# Sheet1.net
KiCad netlist of a schematic drawn in Altium Designer
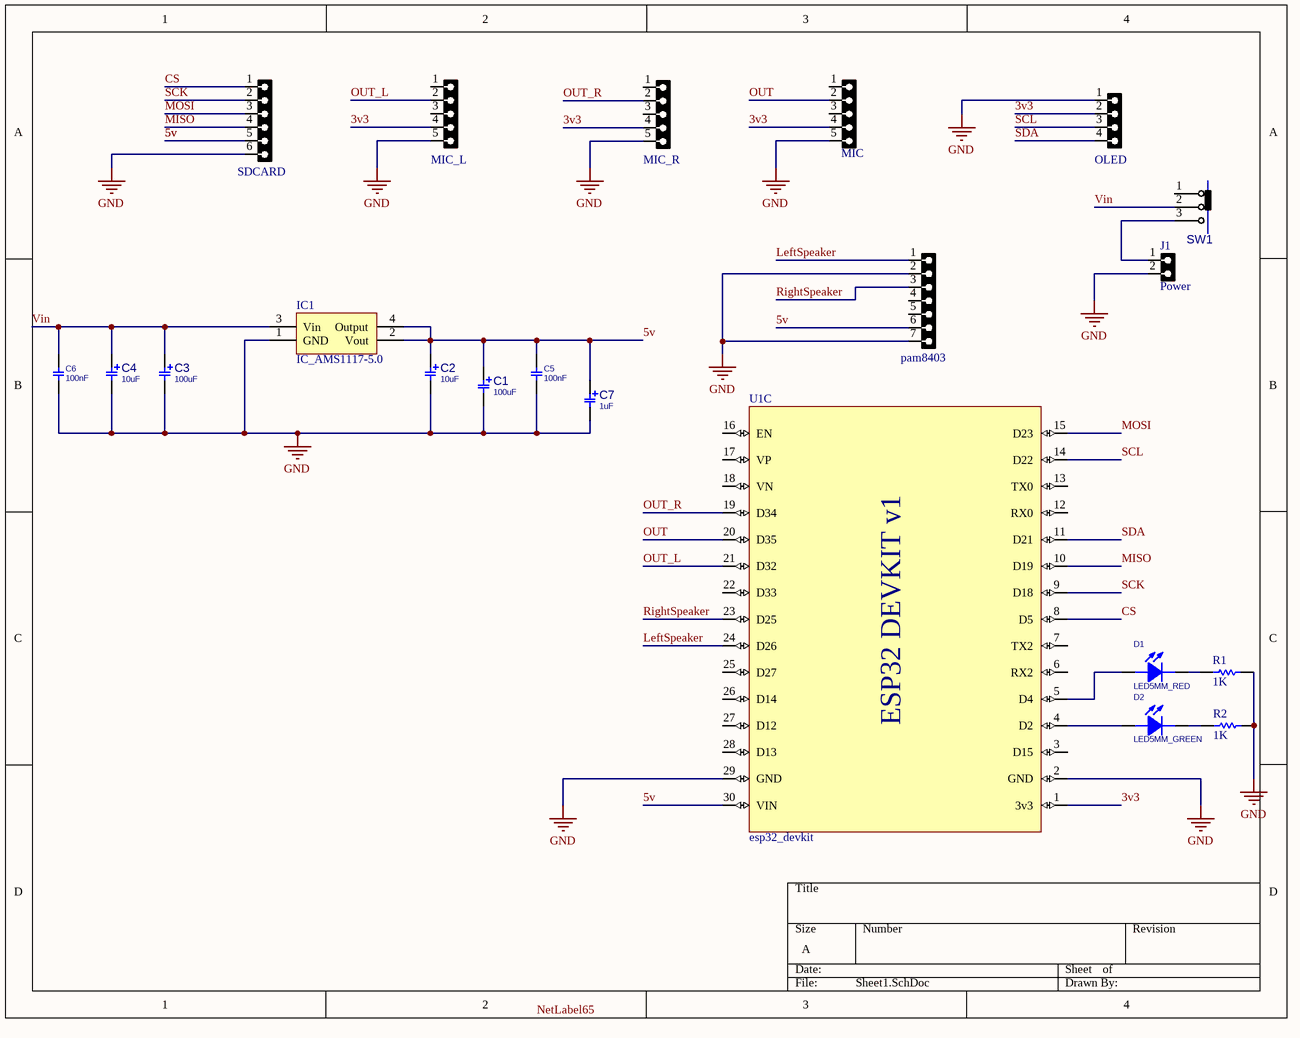
[diagram p0: Sheet1.SchDoc]

(export (version "E")
  (design (tool "Eeschema 10.0.6"))
  (components
    (comp (ref "C1")
      (value "100uF")
      (footprint "C_EL_4X7")
      (description "CAP, THD, ELEC,")
      (fields (field (name "MANF_P#") "MANF_PART#") (field (name "MANF") "MANF"))
      (libsource (lib "passive_thd") (part "CAP_THD_EL_4X7"))
    )
    (comp (ref "C2")
      (value "10uF")
      (footprint "C_EL_4X7")
      (description "CAP, THD, ELEC,")
      (fields (field (name "MANF_P#") "MANF_PART#") (field (name "MANF") "MANF"))
      (libsource (lib "passive_thd") (part "CAP_THD_EL_4X7"))
    )
    (comp (ref "C3")
      (value "100uF")
      (footprint "C_EL_4X7")
      (description "CAP, THD, ELEC,")
      (fields (field (name "MANF_P#") "MANF_PART#") (field (name "MANF") "MANF"))
      (libsource (lib "passive_thd") (part "CAP_THD_EL_4X7"))
    )
    (comp (ref "C4")
      (value "10uF")
      (footprint "C_EL_4X7")
      (description "CAP, THD, ELEC,")
      (fields (field (name "MANF_P#") "MANF_PART#") (field (name "MANF") "MANF"))
      (libsource (lib "passive_thd") (part "CAP_THD_EL_4X7"))
    )
    (comp (ref "C5")
      (value "100nF")
      (footprint "C_CER_D3")
      (description "CAP, THD, CER MULTI LAYER,")
      (fields (field (name "MANF_P#") "MANF_PART#") (field (name "MANF") "MANF"))
      (libsource (lib "passive_thd") (part "CAP_THD_CERML"))
    )
    (comp (ref "C6")
      (value "100nF")
      (footprint "C_CER_D3")
      (description "CAP, THD, CER MULTI LAYER,")
      (fields (field (name "MANF_P#") "MANF_PART#") (field (name "MANF") "MANF"))
      (libsource (lib "passive_thd") (part "CAP_THD_CERML"))
    )
    (comp (ref "C7")
      (value "1uF")
      (footprint "C_EL_4X7")
      (description "CAP, THD, ELEC,")
      (fields (field (name "MANF_P#") "MANF_PART#") (field (name "MANF") "MANF"))
      (libsource (lib "passive_thd") (part "CAP_THD_EL_4X7"))
    )
    (comp (ref "D1")
      (value "LED5MM_RED")
      (footprint "LED5MM_RED")
      (description "LED LIGHTING")
      (fields (field (name "DESIGNER") "Abbas Basereh"))
      (libsource (lib "General 1") (part "LED5MM"))
    )
    (comp (ref "D2")
      (value "LED5MM_GREEN")
      (footprint "LED5MM_GRN")
      (description "LED LIGHTING")
      (fields (field (name "DESIGNER") "Abbas Basereh"))
      (libsource (lib "General 1") (part "LED5MM"))
    )
    (comp (ref "IC1")
      (value "IC_AMS1117-5.0")
      (footprint "SOT223-4N")
      (description "800mA LOW DROPOUT VOLTAGE REGULATOR")
      (fields
        (field (name "MANUFACTURER") "Advanced Monolithic Systems, Inc.")
        (field (name "DESIGNER") "Eng. Saeid Jorablo")
      )
      (libsource (lib "General 3") (part "IC_AMS1117-5.0"))
    )
    (comp (ref "J1")
      (value "Power")
      (footprint "HDR_F_1X2")
      (description "CONN, HEADER, Female, pitch: 2.54mm, 2POS")
      (libsource (lib "conn_header_2.54_st") (part "HDR_F_1X2"))
    )
    (comp (ref "MIC")
      (value "HDRF5")
      (footprint "HDR_F_1X5")
      (description "CONN, HEADER, Female, pitch: 2.54mm, 5POS")
      (libsource (lib "conn_header_2.54_st") (part "HDR_F_1X5"))
    )
    (comp (ref "MIC_L")
      (value "HDRF5")
      (footprint "HDR_F_1X5")
      (description "CONN, HEADER, Female, pitch: 2.54mm, 5POS")
      (libsource (lib "conn_header_2.54_st") (part "HDR_F_1X5"))
    )
    (comp (ref "MIC_R")
      (value "HDRF5")
      (footprint "HDR_F_1X5")
      (description "CONN, HEADER, Female, pitch: 2.54mm, 5POS")
      (libsource (lib "conn_header_2.54_st") (part "HDR_F_1X5"))
    )
    (comp (ref "OLED")
      (value "HDRF4")
      (footprint "HDR_F_1X4")
      (description "CONN, HEADER, Female, pitch: 2.54mm, 4POS")
      (libsource (lib "conn_header_2.54_st") (part "HDR_F_1X4"))
    )
    (comp (ref "pam8403")
      (value "HDRF7")
      (footprint "HDR_F_1X7")
      (description "CONN, HEADER, Female, pitch: 2.54mm, 7POS")
      (libsource (lib "conn_header_2.54_st") (part "HDR_F_1X7"))
    )
    (comp (ref "R1")
      (value "1K")
      (footprint "Axial 0_5W 5_0mm")
      (description "RES Axial 0.5W")
      (fields (field (name "DESIGNER") "Abbas Basereh"))
      (libsource (lib "General 1") (part "RES Axial 0.5W"))
    )
    (comp (ref "R2")
      (value "1K")
      (footprint "Axial 0_5W 5_0mm")
      (description "RES Axial 0.5W")
      (fields (field (name "DESIGNER") "Abbas Basereh"))
      (libsource (lib "General 1") (part "RES Axial 0.5W"))
    )
    (comp (ref "SDCARD")
      (value "HDRF6")
      (footprint "HDR_F_1X6")
      (description "CONN, HEADER, Female, pitch: 2.54mm, 6POS")
      (libsource (lib "conn_header_2.54_st") (part "HDR_F_1X6"))
    )
    (comp (ref "SW1")
      (value "SlideSwitch")
      (footprint "SWSLIDT_SPDT_S_8X4")
      (description "SWITCH, SLIDE, SPDT, 8.6X4.3mm, THD")
      (fields (field (name "MANF") "C&K") (field (name "MANF_PART#") "OS102011MS2QN1"))
      (libsource (lib "switch_slide") (part "SWSLIDT_SPDT_S_8X4"))
    )
    (comp (ref "U1")
      (value "esp32_devkit")
      (footprint "esp32_devkit")
      (libsource (lib "Integrated_Library1") (part "esp32_devkit"))
    )
  )
  (nets
    (net (code "1") (name "/3v3") (class "Default")
      (node (ref "MIC") (pin "4") (pinfunction "4_4") (pintype "passive"))
      (node (ref "MIC_L") (pin "4") (pinfunction "4_4") (pintype "passive"))
      (node (ref "MIC_R") (pin "4") (pinfunction "4_4") (pintype "passive"))
      (node (ref "OLED") (pin "2") (pinfunction "2_2") (pintype "passive"))
      (node (ref "U1") (pin "1") (pinfunction "3v3_1") (pintype "bidirectional"))
    )
    (net (code "2") (name "/5v") (class "Default")
      (node (ref "C1") (pin "1") (pinfunction "1_1") (pintype "passive"))
      (node (ref "C2") (pin "1") (pinfunction "1_1") (pintype "passive"))
      (node (ref "C5") (pin "2") (pinfunction "2_2") (pintype "passive"))
      (node (ref "C7") (pin "1") (pinfunction "1_1") (pintype "passive"))
      (node (ref "IC1") (pin "2") (pinfunction "Vout_2") (pintype "passive"))
      (node (ref "IC1") (pin "4") (pinfunction "Output_4") (pintype "passive"))
      (node (ref "SDCARD") (pin "5") (pinfunction "5_5") (pintype "passive"))
      (node (ref "U1") (pin "30") (pinfunction "VIN_30") (pintype "bidirectional"))
      (node (ref "pam8403") (pin "6") (pinfunction "6_6") (pintype "passive"))
    )
    (net (code "3") (name "/CS") (class "Default")
      (node (ref "SDCARD") (pin "1") (pinfunction "1_1") (pintype "passive"))
      (node (ref "U1") (pin "8") (pinfunction "D5_8") (pintype "bidirectional"))
    )
    (net (code "4") (name "/LeftSpeaker") (class "Default")
      (node (ref "U1") (pin "24") (pinfunction "D26_24") (pintype "bidirectional"))
      (node (ref "pam8403") (pin "1") (pinfunction "1_1") (pintype "passive"))
    )
    (net (code "5") (name "/MISO") (class "Default")
      (node (ref "SDCARD") (pin "4") (pinfunction "4_4") (pintype "passive"))
      (node (ref "U1") (pin "10") (pinfunction "D19_10") (pintype "bidirectional"))
    )
    (net (code "6") (name "/MOSI") (class "Default")
      (node (ref "SDCARD") (pin "3") (pinfunction "3_3") (pintype "passive"))
      (node (ref "U1") (pin "15") (pinfunction "D23_15") (pintype "bidirectional"))
    )
    (net (code "8") (name "/OUT") (class "Default")
      (node (ref "MIC") (pin "2") (pinfunction "2_2") (pintype "passive"))
      (node (ref "U1") (pin "20") (pinfunction "D35_20") (pintype "bidirectional"))
    )
    (net (code "9") (name "/OUT_L") (class "Default")
      (node (ref "MIC_L") (pin "2") (pinfunction "2_2") (pintype "passive"))
      (node (ref "U1") (pin "21") (pinfunction "D32_21") (pintype "bidirectional"))
    )
    (net (code "10") (name "/OUT_R") (class "Default")
      (node (ref "MIC_R") (pin "2") (pinfunction "2_2") (pintype "passive"))
      (node (ref "U1") (pin "19") (pinfunction "D34_19") (pintype "bidirectional"))
    )
    (net (code "11") (name "/RightSpeaker") (class "Default")
      (node (ref "U1") (pin "23") (pinfunction "D25_23") (pintype "bidirectional"))
      (node (ref "pam8403") (pin "3") (pinfunction "3_3") (pintype "passive"))
    )
    (net (code "12") (name "/SCK") (class "Default")
      (node (ref "SDCARD") (pin "2") (pinfunction "2_2") (pintype "passive"))
      (node (ref "U1") (pin "9") (pinfunction "D18_9") (pintype "bidirectional"))
    )
    (net (code "13") (name "/SCL") (class "Default")
      (node (ref "OLED") (pin "3") (pinfunction "3_3") (pintype "passive"))
      (node (ref "U1") (pin "14") (pinfunction "D22_14") (pintype "bidirectional"))
    )
    (net (code "14") (name "/SDA") (class "Default")
      (node (ref "OLED") (pin "4") (pinfunction "4_4") (pintype "passive"))
      (node (ref "U1") (pin "11") (pinfunction "D21_11") (pintype "bidirectional"))
    )
    (net (code "15") (name "/Vin") (class "Default")
      (node (ref "C3") (pin "1") (pinfunction "1_1") (pintype "passive"))
      (node (ref "C4") (pin "1") (pinfunction "1_1") (pintype "passive"))
      (node (ref "C6") (pin "2") (pinfunction "2_2") (pintype "passive"))
      (node (ref "IC1") (pin "3") (pinfunction "Vin_3") (pintype "passive"))
      (node (ref "SW1") (pin "2") (pinfunction "P3_2") (pintype "passive"))
    )
    (net (code "16") (name "GND") (class "Default")
      (node (ref "C1") (pin "2") (pinfunction "2_2") (pintype "passive"))
      (node (ref "C2") (pin "2") (pinfunction "2_2") (pintype "passive"))
      (node (ref "C3") (pin "2") (pinfunction "2_2") (pintype "passive"))
      (node (ref "C4") (pin "2") (pinfunction "2_2") (pintype "passive"))
      (node (ref "C5") (pin "1") (pinfunction "1_1") (pintype "passive"))
      (node (ref "C6") (pin "1") (pinfunction "1_1") (pintype "passive"))
      (node (ref "C7") (pin "2") (pinfunction "2_2") (pintype "passive"))
      (node (ref "IC1") (pin "1") (pinfunction "GND_1") (pintype "passive"))
      (node (ref "J1") (pin "2") (pinfunction "2_2") (pintype "passive"))
      (node (ref "MIC") (pin "5") (pinfunction "5_5") (pintype "passive"))
      (node (ref "MIC_L") (pin "5") (pinfunction "5_5") (pintype "passive"))
      (node (ref "MIC_R") (pin "5") (pinfunction "5_5") (pintype "passive"))
      (node (ref "OLED") (pin "1") (pinfunction "1_1") (pintype "passive"))
      (node (ref "R1") (pin "2") (pinfunction "2_2") (pintype "passive"))
      (node (ref "R2") (pin "2") (pinfunction "2_2") (pintype "passive"))
      (node (ref "SDCARD") (pin "6") (pinfunction "6_6") (pintype "passive"))
      (node (ref "U1") (pin "2") (pinfunction "GND_2") (pintype "bidirectional"))
      (node (ref "U1") (pin "29") (pinfunction "GND_29") (pintype "bidirectional"))
      (node (ref "pam8403") (pin "2") (pinfunction "2_2") (pintype "passive"))
      (node (ref "pam8403") (pin "7") (pinfunction "7_7") (pintype "passive"))
    )
    (net (code "17") (name "Net-(D1-ANODE)") (class "Default")
      (node (ref "D1") (pin "1") (pinfunction "ANODE_1") (pintype "passive"))
      (node (ref "U1") (pin "5") (pinfunction "D4_5") (pintype "bidirectional"))
    )
    (net (code "18") (name "Net-(D1-CATHODE)") (class "Default")
      (node (ref "D1") (pin "2") (pinfunction "CATHODE_2") (pintype "passive"))
      (node (ref "R1") (pin "1") (pinfunction "1_1") (pintype "passive"))
    )
    (net (code "19") (name "Net-(D2-ANODE)") (class "Default")
      (node (ref "D2") (pin "1") (pinfunction "ANODE_1") (pintype "passive"))
      (node (ref "U1") (pin "4") (pinfunction "D2_4") (pintype "bidirectional"))
    )
    (net (code "20") (name "Net-(D2-CATHODE)") (class "Default")
      (node (ref "D2") (pin "2") (pinfunction "CATHODE_2") (pintype "passive"))
      (node (ref "R2") (pin "1") (pinfunction "1_1") (pintype "passive"))
    )
    (net (code "21") (name "Net-(SW1-P4)") (class "Default")
      (node (ref "J1") (pin "1") (pinfunction "1_1") (pintype "passive"))
      (node (ref "SW1") (pin "3") (pinfunction "P4_3") (pintype "passive"))
    )
    (net (code "22") (name "unconnected-(MIC-Pad1)") (class "Default")
      (node (ref "MIC") (pin "1") (pinfunction "1_1") (pintype "passive"))
    )
    (net (code "23") (name "unconnected-(MIC-Pad3)") (class "Default")
      (node (ref "MIC") (pin "3") (pinfunction "3_3") (pintype "passive"))
    )
    (net (code "24") (name "unconnected-(MIC_L-Pad1)") (class "Default")
      (node (ref "MIC_L") (pin "1") (pinfunction "1_1") (pintype "passive"))
    )
    (net (code "25") (name "unconnected-(MIC_L-Pad3)") (class "Default")
      (node (ref "MIC_L") (pin "3") (pinfunction "3_3") (pintype "passive"))
    )
    (net (code "26") (name "unconnected-(MIC_R-Pad1)") (class "Default")
      (node (ref "MIC_R") (pin "1") (pinfunction "1_1") (pintype "passive"))
    )
    (net (code "27") (name "unconnected-(MIC_R-Pad3)") (class "Default")
      (node (ref "MIC_R") (pin "3") (pinfunction "3_3") (pintype "passive"))
    )
    (net (code "28") (name "unconnected-(SW1-P1-Pad1)") (class "Default")
      (node (ref "SW1") (pin "1") (pinfunction "P1_1") (pintype "passive"))
    )
    (net (code "29") (name "unconnected-(U1C-D12-Pad27)") (class "Default")
      (node (ref "U1") (pin "27") (pinfunction "D12_27") (pintype "bidirectional"))
    )
    (net (code "30") (name "unconnected-(U1C-D13-Pad28)") (class "Default")
      (node (ref "U1") (pin "28") (pinfunction "D13_28") (pintype "bidirectional"))
    )
    (net (code "31") (name "unconnected-(U1C-D14-Pad26)") (class "Default")
      (node (ref "U1") (pin "26") (pinfunction "D14_26") (pintype "bidirectional"))
    )
    (net (code "32") (name "unconnected-(U1C-D15-Pad3)") (class "Default")
      (node (ref "U1") (pin "3") (pinfunction "D15_3") (pintype "bidirectional"))
    )
    (net (code "33") (name "unconnected-(U1C-D27-Pad25)") (class "Default")
      (node (ref "U1") (pin "25") (pinfunction "D27_25") (pintype "bidirectional"))
    )
    (net (code "34") (name "unconnected-(U1C-D33-Pad22)") (class "Default")
      (node (ref "U1") (pin "22") (pinfunction "D33_22") (pintype "bidirectional"))
    )
    (net (code "35") (name "unconnected-(U1C-EN-Pad16)") (class "Default")
      (node (ref "U1") (pin "16") (pinfunction "EN_16") (pintype "bidirectional"))
    )
    (net (code "36") (name "unconnected-(U1C-RX0-Pad12)") (class "Default")
      (node (ref "U1") (pin "12") (pinfunction "RX0_12") (pintype "bidirectional"))
    )
    (net (code "37") (name "unconnected-(U1C-RX2-Pad6)") (class "Default")
      (node (ref "U1") (pin "6") (pinfunction "RX2_6") (pintype "bidirectional"))
    )
    (net (code "38") (name "unconnected-(U1C-TX0-Pad13)") (class "Default")
      (node (ref "U1") (pin "13") (pinfunction "TX0_13") (pintype "bidirectional"))
    )
    (net (code "39") (name "unconnected-(U1C-TX2-Pad7)") (class "Default")
      (node (ref "U1") (pin "7") (pinfunction "TX2_7") (pintype "bidirectional"))
    )
    (net (code "40") (name "unconnected-(U1C-VN-Pad18)") (class "Default")
      (node (ref "U1") (pin "18") (pinfunction "VN_18") (pintype "bidirectional"))
    )
    (net (code "41") (name "unconnected-(U1C-VP-Pad17)") (class "Default")
      (node (ref "U1") (pin "17") (pinfunction "VP_17") (pintype "bidirectional"))
    )
    (net (code "42") (name "unconnected-(pam8403-Pad4)") (class "Default")
      (node (ref "pam8403") (pin "4") (pinfunction "4_4") (pintype "passive"))
    )
    (net (code "43") (name "unconnected-(pam8403-Pad5)") (class "Default")
      (node (ref "pam8403") (pin "5") (pinfunction "5_5") (pintype "passive"))
    )
  )
)
